# design.net
KiCad netlist of a schematic drawn in Altium Designer
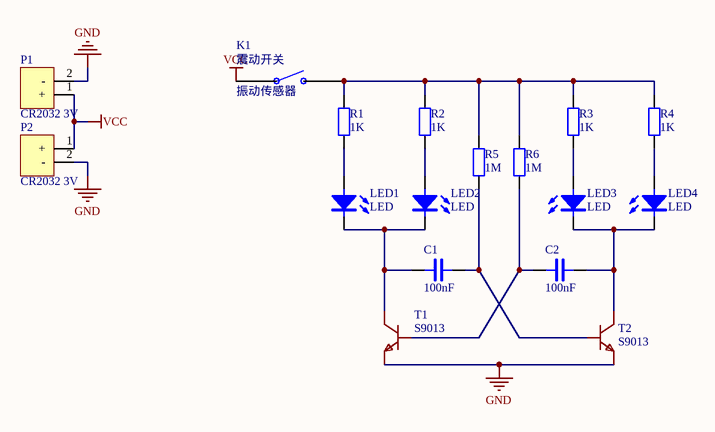
[diagram p0: 发光陀螺.SchDoc]

(export (version "E")
  (design (tool "Eeschema 10.0.6"))
  (components
    (comp (ref "C1")
      (value "100nF")
      (footprint "0603_C")
      (description "Capacitor")
      (libsource (lib "General") (part "CAP"))
    )
    (comp (ref "C2")
      (value "100nF")
      (footprint "0603_C")
      (description "Capacitor")
      (libsource (lib "General") (part "CAP"))
    )
    (comp (ref "K1")
      (value "振动传感器")
      (footprint "SW-28020")
      (description "Key,振荡传感器")
      (libsource (lib "General") (part "振动传感器"))
    )
    (comp (ref "LED1")
      (value "LED")
      (footprint "LED 2.54mm 直插式 5mm")
      (libsource (lib "General") (part "LED"))
    )
    (comp (ref "LED2")
      (value "LED")
      (footprint "LED 2.54mm 直插式 5mm")
      (libsource (lib "General") (part "LED"))
    )
    (comp (ref "LED3")
      (value "LED")
      (footprint "LED 2.54mm 直插式 5mm")
      (libsource (lib "General") (part "LED"))
    )
    (comp (ref "LED4")
      (value "LED")
      (footprint "LED 2.54mm 直插式 5mm")
      (libsource (lib "General") (part "LED"))
    )
    (comp (ref "P1")
      (value "CR2032 3V")
      (footprint "CR2032_电池座")
      (description "电源接口")
      (libsource (lib "General") (part "纽扣电池电池座"))
    )
    (comp (ref "P2")
      (value "CR2032 3V")
      (footprint "CR2032_电池座")
      (description "电源接口")
      (libsource (lib "") (part "纽扣电池电池座_1"))
    )
    (comp (ref "R1")
      (value "1K")
      (footprint "0603_R")
      (description "Resistor")
      (libsource (lib "General") (part "RES"))
    )
    (comp (ref "R2")
      (value "1K")
      (footprint "0603_R")
      (description "Resistor")
      (libsource (lib "General") (part "RES"))
    )
    (comp (ref "R3")
      (value "1K")
      (footprint "0603_R")
      (description "Resistor")
      (libsource (lib "") (part "RES_1"))
    )
    (comp (ref "R4")
      (value "1K")
      (footprint "0603_R")
      (description "Resistor")
      (libsource (lib "") (part "RES_1"))
    )
    (comp (ref "R5")
      (value "1M")
      (footprint "0603_R")
      (description "Resistor")
      (libsource (lib "General") (part "RES"))
    )
    (comp (ref "R6")
      (value "1M")
      (footprint "0603_R")
      (description "Resistor")
      (libsource (lib "") (part "RES_1"))
    )
    (comp (ref "T1")
      (value "S9013")
      (footprint "SOT-23-3")
      (description "NPN")
      (libsource (lib "General") (part "S9013"))
    )
    (comp (ref "T2")
      (value "S9013")
      (footprint "SOT-23-3")
      (description "NPN")
      (libsource (lib "General") (part "S9013"))
    )
  )
  (nets
    (net (code "1") (name "GND") (class "Default")
      (node (ref "P1") (pin "2") (pinfunction "-_2") (pintype "passive"))
      (node (ref "P2") (pin "2") (pinfunction "-_2") (pintype "passive"))
      (node (ref "T1") (pin "2") (pinfunction "E_2") (pintype "passive"))
      (node (ref "T2") (pin "2") (pinfunction "E_2") (pintype "passive"))
    )
    (net (code "2") (name "Net-(K1-Pad2)") (class "Default")
      (node (ref "K1") (pin "2") (pinfunction "2_2") (pintype "passive"))
      (node (ref "R1") (pin "2") (pinfunction "2_2") (pintype "passive"))
      (node (ref "R2") (pin "2") (pinfunction "2_2") (pintype "passive"))
      (node (ref "R3") (pin "2") (pinfunction "2_2") (pintype "passive"))
      (node (ref "R4") (pin "2") (pinfunction "2_2") (pintype "passive"))
      (node (ref "R5") (pin "2") (pinfunction "2_2") (pintype "passive"))
      (node (ref "R6") (pin "2") (pinfunction "2_2") (pintype "passive"))
    )
    (net (code "3") (name "Net-(LED1-A)") (class "Default")
      (node (ref "LED1") (pin "1") (pinfunction "A_1") (pintype "passive"))
      (node (ref "R1") (pin "1") (pinfunction "1_1") (pintype "passive"))
    )
    (net (code "4") (name "Net-(LED1-C)") (class "Default")
      (node (ref "C1") (pin "1") (pinfunction "1_1") (pintype "passive"))
      (node (ref "LED1") (pin "2") (pinfunction "C_2") (pintype "passive"))
      (node (ref "LED2") (pin "2") (pinfunction "C_2") (pintype "passive"))
      (node (ref "T1") (pin "3") (pinfunction "C_3") (pintype "passive"))
    )
    (net (code "5") (name "Net-(LED2-A)") (class "Default")
      (node (ref "LED2") (pin "1") (pinfunction "A_1") (pintype "passive"))
      (node (ref "R2") (pin "1") (pinfunction "1_1") (pintype "passive"))
    )
    (net (code "6") (name "Net-(LED3-A)") (class "Default")
      (node (ref "LED3") (pin "1") (pinfunction "A_1") (pintype "passive"))
      (node (ref "R3") (pin "1") (pinfunction "1_1") (pintype "passive"))
    )
    (net (code "7") (name "Net-(LED3-C)") (class "Default")
      (node (ref "C2") (pin "1") (pinfunction "1_1") (pintype "passive"))
      (node (ref "LED3") (pin "2") (pinfunction "C_2") (pintype "passive"))
      (node (ref "LED4") (pin "2") (pinfunction "C_2") (pintype "passive"))
      (node (ref "T2") (pin "3") (pinfunction "C_3") (pintype "passive"))
    )
    (net (code "8") (name "Net-(LED4-A)") (class "Default")
      (node (ref "LED4") (pin "1") (pinfunction "A_1") (pintype "passive"))
      (node (ref "R4") (pin "1") (pinfunction "1_1") (pintype "passive"))
    )
    (net (code "9") (name "Net-(T1-B)") (class "Default")
      (node (ref "C2") (pin "2") (pinfunction "2_2") (pintype "passive"))
      (node (ref "R6") (pin "1") (pinfunction "1_1") (pintype "passive"))
      (node (ref "T1") (pin "1") (pinfunction "B_1") (pintype "passive"))
    )
    (net (code "10") (name "Net-(T2-B)") (class "Default")
      (node (ref "C1") (pin "2") (pinfunction "2_2") (pintype "passive"))
      (node (ref "R5") (pin "1") (pinfunction "1_1") (pintype "passive"))
      (node (ref "T2") (pin "1") (pinfunction "B_1") (pintype "passive"))
    )
    (net (code "11") (name "VCC") (class "Default")
      (node (ref "K1") (pin "1") (pinfunction "1_1") (pintype "passive"))
      (node (ref "P1") (pin "1") (pinfunction "+_1") (pintype "passive"))
      (node (ref "P2") (pin "1") (pinfunction "+_1") (pintype "passive"))
    )
  )
)
